# control_board.net
KiCad netlist of a schematic drawn in Altium Designer
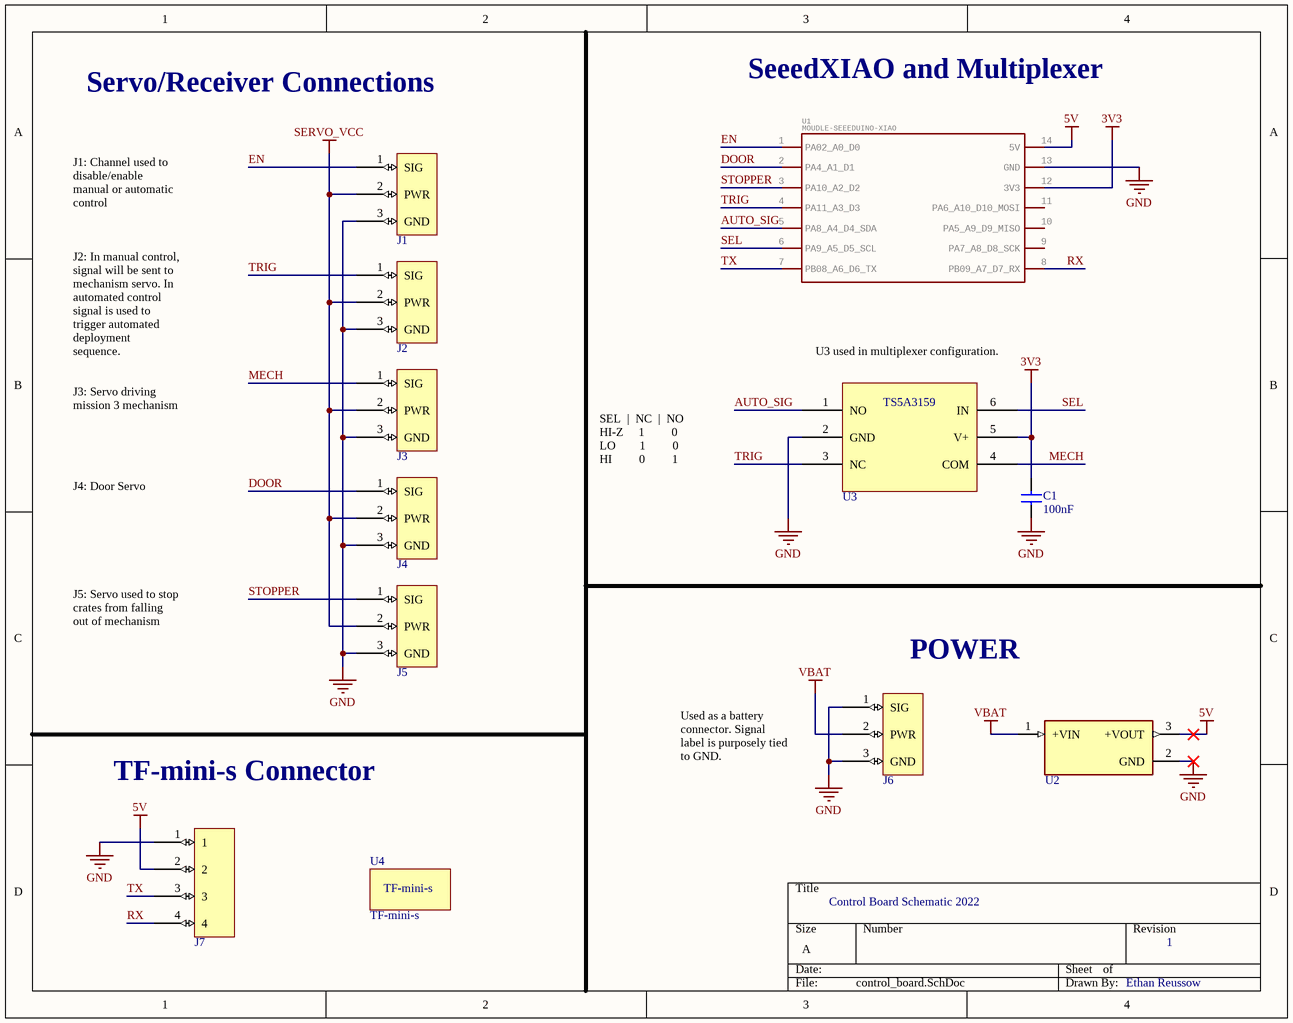
[diagram p0: control_board.SchDoc]

(export (version "E")
  (design (tool "Eeschema 10.0.6"))
  (components
    (comp (ref "C1")
      (value "100nF")
      (footprint "CAPC0603")
      (fields (field (name "Comment") "Cap"))
      (libsource (lib "Passives") (part "Cap"))
    )
    (comp (ref "J1")
      (value "3x1 conn")
      (footprint "1x3 2.54MM")
      (description "Pinout for a servo connector")
      (libsource (lib "Control_Board") (part "3x1 conn"))
    )
    (comp (ref "J2")
      (value "3x1 conn")
      (footprint "1x3 2.54MM")
      (description "Pinout for a servo connector")
      (libsource (lib "Control_Board") (part "3x1 conn"))
    )
    (comp (ref "J3")
      (value "3x1 conn")
      (footprint "1x3 2.54MM")
      (description "Pinout for a servo connector")
      (libsource (lib "Control_Board") (part "3x1 conn"))
    )
    (comp (ref "J4")
      (value "3x1 conn")
      (footprint "1x3 2.54MM")
      (description "Pinout for a servo connector")
      (libsource (lib "Control_Board") (part "3x1 conn"))
    )
    (comp (ref "J5")
      (value "3x1 conn")
      (footprint "1x3 2.54MM")
      (description "Pinout for a servo connector")
      (libsource (lib "Control_Board") (part "3x1 conn"))
    )
    (comp (ref "J6")
      (value "3x1 conn")
      (footprint "1x3 2.54MM")
      (description "Pinout for a servo connector")
      (libsource (lib "Control_Board") (part "3x1 conn"))
    )
    (comp (ref "J7")
      (value "4x1 conn")
      (footprint "1x4 2.54mm")
      (libsource (lib "Control_Board") (part "4x1 conn"))
    )
    (comp (ref "U1")
      (value "MOUDLE-SEEEDUINO-XIAO")
      (footprint "MOUDLE14P-2-54-21X17-8MM")
      (libsource (lib "Control_Board") (part "MOUDLE-SEEEDUINO-XIAO"))
    )
    (comp (ref "U2")
      (value "TSR1-2450")
      (footprint "Control_Board:CONV_TSR1-2450")
      (description "Non-Isolated PoL Module DC DC Converter 1 Output 5V 1A 7V - 36V Input")
      (fields (field (name "MF") "Traco Power") (field (name "MP") "TSR 1-2450"))
      (libsource (lib "Control_Board") (part "TSR1-2450"))
    )
    (comp (ref "U3")
      (value "TS5A3159DBVR")
      (footprint "SOT23-6")
      (libsource (lib "Control_Board") (part "TS5A3159DBVR"))
    )
    (comp (ref "U4")
      (value "TF-mini-s")
      (footprint "TF-mini-s")
      (libsource (lib "Control_Board") (part "TF-mini-s"))
    )
  )
  (nets
    (net (code "1") (name "/AUTO_SIG") (class "Default")
      (node (ref "U1") (pin "5") (pinfunction "PA8_A4_D4_SDA_5") (pintype "bidirectional"))
      (node (ref "U3") (pin "1") (pinfunction "NO_1") (pintype "passive"))
    )
    (net (code "2") (name "/DOOR") (class "Default")
      (node (ref "J4") (pin "1") (pinfunction "SIG_1") (pintype "bidirectional"))
      (node (ref "U1") (pin "2") (pinfunction "PA4_A1_D1_2") (pintype "bidirectional"))
    )
    (net (code "3") (name "/EN") (class "Default")
      (node (ref "J1") (pin "1") (pinfunction "SIG_1") (pintype "bidirectional"))
      (node (ref "U1") (pin "1") (pinfunction "PA02_A0_D0_1") (pintype "bidirectional"))
    )
    (net (code "4") (name "/MECH") (class "Default")
      (node (ref "J3") (pin "1") (pinfunction "SIG_1") (pintype "bidirectional"))
      (node (ref "U3") (pin "4") (pinfunction "COM_4") (pintype "passive"))
    )
    (net (code "5") (name "/RX") (class "Default")
      (node (ref "J7") (pin "4") (pinfunction "4_4") (pintype "bidirectional"))
      (node (ref "U1") (pin "8") (pinfunction "PB09_A7_D7_RX_8") (pintype "bidirectional"))
    )
    (net (code "6") (name "/SEL") (class "Default")
      (node (ref "U1") (pin "6") (pinfunction "PA9_A5_D5_SCL_6") (pintype "bidirectional"))
      (node (ref "U3") (pin "6") (pinfunction "IN_6") (pintype "passive"))
    )
    (net (code "7") (name "/STOPPER") (class "Default")
      (node (ref "J5") (pin "1") (pinfunction "SIG_1") (pintype "bidirectional"))
      (node (ref "U1") (pin "3") (pinfunction "PA10_A2_D2_3") (pintype "bidirectional"))
    )
    (net (code "8") (name "/TRIG") (class "Default")
      (node (ref "J2") (pin "1") (pinfunction "SIG_1") (pintype "bidirectional"))
      (node (ref "U1") (pin "4") (pinfunction "PA11_A3_D3_4") (pintype "bidirectional"))
      (node (ref "U3") (pin "3") (pinfunction "NC_3") (pintype "passive"))
    )
    (net (code "9") (name "/TX") (class "Default")
      (node (ref "J7") (pin "3") (pinfunction "3_3") (pintype "bidirectional"))
      (node (ref "U1") (pin "7") (pinfunction "PB08_A6_D6_TX_7") (pintype "bidirectional"))
    )
    (net (code "10") (name "3V3") (class "Default")
      (node (ref "C1") (pin "1") (pinfunction "A_1") (pintype "passive"))
      (node (ref "U1") (pin "12") (pinfunction "3V3_12") (pintype "bidirectional"))
      (node (ref "U3") (pin "5") (pinfunction "V+_5") (pintype "passive"))
    )
    (net (code "11") (name "5V") (class "Default")
      (node (ref "J7") (pin "2") (pinfunction "2_2") (pintype "bidirectional"))
      (node (ref "U1") (pin "14") (pinfunction "5V_14") (pintype "bidirectional"))
      (node (ref "U2") (pin "3") (pinfunction "+VOUT_3") (pintype "output"))
    )
    (net (code "12") (name "GND") (class "Default")
      (node (ref "C1") (pin "2") (pinfunction "B_2") (pintype "passive"))
      (node (ref "J1") (pin "3") (pinfunction "GND_3") (pintype "bidirectional"))
      (node (ref "J2") (pin "3") (pinfunction "GND_3") (pintype "bidirectional"))
      (node (ref "J3") (pin "3") (pinfunction "GND_3") (pintype "bidirectional"))
      (node (ref "J4") (pin "3") (pinfunction "GND_3") (pintype "bidirectional"))
      (node (ref "J5") (pin "3") (pinfunction "GND_3") (pintype "bidirectional"))
      (node (ref "J6") (pin "1") (pinfunction "SIG_1") (pintype "bidirectional"))
      (node (ref "J6") (pin "3") (pinfunction "GND_3") (pintype "bidirectional"))
      (node (ref "J7") (pin "1") (pinfunction "1_1") (pintype "bidirectional"))
      (node (ref "U1") (pin "13") (pinfunction "GND_13") (pintype "bidirectional"))
      (node (ref "U2") (pin "2") (pinfunction "GND_2") (pintype "power_in"))
      (node (ref "U3") (pin "2") (pinfunction "GND_2") (pintype "passive"))
    )
    (net (code "13") (name "SERVO_VCC") (class "Default")
      (node (ref "J1") (pin "2") (pinfunction "PWR_2") (pintype "bidirectional"))
      (node (ref "J2") (pin "2") (pinfunction "PWR_2") (pintype "bidirectional"))
      (node (ref "J3") (pin "2") (pinfunction "PWR_2") (pintype "bidirectional"))
      (node (ref "J4") (pin "2") (pinfunction "PWR_2") (pintype "bidirectional"))
      (node (ref "J5") (pin "2") (pinfunction "PWR_2") (pintype "bidirectional"))
    )
    (net (code "14") (name "VBAT") (class "Default")
      (node (ref "J6") (pin "2") (pinfunction "PWR_2") (pintype "bidirectional"))
      (node (ref "U2") (pin "1") (pinfunction "+VIN_1") (pintype "input"))
    )
    (net (code "15") (name "unconnected-(U1-PA5_A9_D9_MISO-Pad10)") (class "Default")
      (node (ref "U1") (pin "10") (pinfunction "PA5_A9_D9_MISO_10") (pintype "bidirectional"))
    )
    (net (code "16") (name "unconnected-(U1-PA6_A10_D10_MOSI-Pad11)") (class "Default")
      (node (ref "U1") (pin "11") (pinfunction "PA6_A10_D10_MOSI_11") (pintype "bidirectional"))
    )
    (net (code "17") (name "unconnected-(U1-PA7_A8_D8_SCK-Pad9)") (class "Default")
      (node (ref "U1") (pin "9") (pinfunction "PA7_A8_D8_SCK_9") (pintype "bidirectional"))
    )
  )
)
